# intanRHS2116.net
KiCad netlist of a schematic drawn in Altium Designer
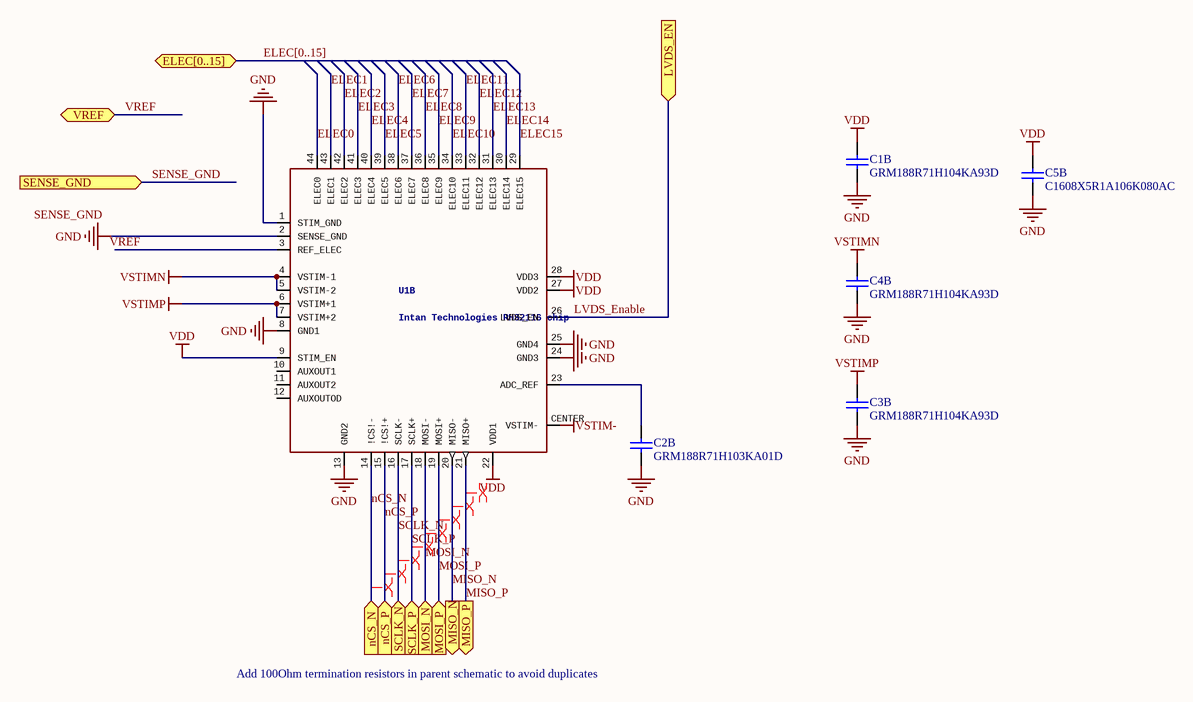
[diagram p0: intanRHS2116.SchDoc]

(export (version "E")
  (design (tool "Eeschema 10.0.6"))
  (components
    (comp (ref "C1B")
      (value "GRM188R71H104KA93D")
      (footprint "CAPC1608X90X35ML10T15")
      (description "Chip Capacitor, 0.1 uF, +/- 10%, 50 V, -55 to 125 degC, 0603 (1608 Metric), RoHS, Tape and Reel")
      (fields (field (name "TOLERANCE") "10%") (field (name "VOLTAGE") "50V"))
      (libsource (lib "Altium Content Vault") (part "CAP-NP-2"))
    )
    (comp (ref "C2B")
      (value "GRM188R71H103KA01D")
      (footprint "CAPC1608X90X35ML10T15")
      (description "Chip Capacitor, 10 nF, +/- 10%, 50 V, -55 to 125 degC, 0603 (1608 Metric), RoHS, Tape and Reel")
      (fields (field (name "VOLTAGE") "50V") (field (name "TOLERANCE") "10%"))
      (libsource (lib "Altium Content Vault") (part "CAP-NP-2"))
    )
    (comp (ref "C3B")
      (value "GRM188R71H104KA93D")
      (footprint "CAPC1608X90X35ML10T15")
      (description "Chip Capacitor, 0.1 uF, +/- 10%, 50 V, -55 to 125 degC, 0603 (1608 Metric), RoHS, Tape and Reel")
      (fields (field (name "TOLERANCE") "10%") (field (name "VOLTAGE") "50V"))
      (libsource (lib "Altium Content Vault") (part "CAP-NP-2"))
    )
    (comp (ref "C4B")
      (value "GRM188R71H104KA93D")
      (footprint "CAPC1608X90X35ML10T15")
      (description "Chip Capacitor, 0.1 uF, +/- 10%, 50 V, -55 to 125 degC, 0603 (1608 Metric), RoHS, Tape and Reel")
      (fields (field (name "TOLERANCE") "10%") (field (name "VOLTAGE") "50V"))
      (libsource (lib "Altium Content Vault") (part "CAP-NP-2"))
    )
    (comp (ref "C5B")
      (value "C1608X5R1A106K080AC")
      (footprint "CAPC1608X90X20ML10")
      (description "Chip Capacitor, 10 uF, +/- 10%, 10 V, -55 to 85 degC, 0603 (1608 Metric), RoHS, Tape and Reel")
      (fields
        (field (name "PCN PART NUMBER") "MLCCPartNumberChange30/Nov/2012")
        (field (name "TOLERANCE") "±10%")
      )
      (libsource (lib "Altium Content Vault") (part "CAP-NP-2"))
    )
    (comp (ref "U1B")
      (value "Intan Technologies RHS2116 chip")
      (footprint "intan_rhs2116:QFN44_7_X_7")
      (fields
        (field (name "MANUFACTURER") "Intan Technologies")
        (field (name "MANUFACTURER PART NUMBER") "RHS2116")
      )
      (libsource (lib "intan_rhs2116") (part "RHS2116_QFN"))
    )
  )
  (nets
    (net (code "1") (name "/ELEC0") (class "Default")
      (node (ref "U1B") (pin "44") (pinfunction "ELEC0_44") (pintype "passive"))
    )
    (net (code "2") (name "/ELEC1") (class "Default")
      (node (ref "U1B") (pin "43") (pinfunction "ELEC1_43") (pintype "passive"))
    )
    (net (code "3") (name "/ELEC2") (class "Default")
      (node (ref "U1B") (pin "42") (pinfunction "ELEC2_42") (pintype "passive"))
    )
    (net (code "4") (name "/ELEC3") (class "Default")
      (node (ref "U1B") (pin "41") (pinfunction "ELEC3_41") (pintype "passive"))
    )
    (net (code "5") (name "/ELEC4") (class "Default")
      (node (ref "U1B") (pin "40") (pinfunction "ELEC4_40") (pintype "passive"))
    )
    (net (code "6") (name "/ELEC5") (class "Default")
      (node (ref "U1B") (pin "39") (pinfunction "ELEC5_39") (pintype "passive"))
    )
    (net (code "7") (name "/ELEC6") (class "Default")
      (node (ref "U1B") (pin "38") (pinfunction "ELEC6_38") (pintype "passive"))
    )
    (net (code "8") (name "/ELEC7") (class "Default")
      (node (ref "U1B") (pin "37") (pinfunction "ELEC7_37") (pintype "passive"))
    )
    (net (code "9") (name "/ELEC8") (class "Default")
      (node (ref "U1B") (pin "36") (pinfunction "ELEC8_36") (pintype "passive"))
    )
    (net (code "10") (name "/ELEC9") (class "Default")
      (node (ref "U1B") (pin "35") (pinfunction "ELEC9_35") (pintype "passive"))
    )
    (net (code "11") (name "/ELEC10") (class "Default")
      (node (ref "U1B") (pin "34") (pinfunction "ELEC10_34") (pintype "passive"))
    )
    (net (code "12") (name "/ELEC11") (class "Default")
      (node (ref "U1B") (pin "33") (pinfunction "ELEC11_33") (pintype "passive"))
    )
    (net (code "13") (name "/ELEC12") (class "Default")
      (node (ref "U1B") (pin "32") (pinfunction "ELEC12_32") (pintype "passive"))
    )
    (net (code "14") (name "/ELEC13") (class "Default")
      (node (ref "U1B") (pin "31") (pinfunction "ELEC13_31") (pintype "passive"))
    )
    (net (code "15") (name "/ELEC14") (class "Default")
      (node (ref "U1B") (pin "30") (pinfunction "ELEC14_30") (pintype "passive"))
    )
    (net (code "16") (name "/ELEC15") (class "Default")
      (node (ref "U1B") (pin "29") (pinfunction "ELEC15_29") (pintype "passive"))
    )
    (net (code "18") (name "/LVDS_Enable") (class "Default")
      (node (ref "U1B") (pin "26") (pinfunction "LVDS_EN_26") (pintype "passive"))
    )
    (net (code "19") (name "/MISO_N") (class "Default")
      (node (ref "U1B") (pin "20") (pinfunction "MISO-_20") (pintype "output"))
    )
    (net (code "20") (name "/MISO_P") (class "Default")
      (node (ref "U1B") (pin "21") (pinfunction "MISO+_21") (pintype "output"))
    )
    (net (code "21") (name "/MOSI_N") (class "Default")
      (node (ref "U1B") (pin "18") (pinfunction "MOSI-_18") (pintype "passive"))
    )
    (net (code "22") (name "/MOSI_P") (class "Default")
      (node (ref "U1B") (pin "19") (pinfunction "MOSI+_19") (pintype "passive"))
    )
    (net (code "23") (name "/SCLK_N") (class "Default")
      (node (ref "U1B") (pin "16") (pinfunction "SCLK-_16") (pintype "passive"))
    )
    (net (code "24") (name "/SCLK_P") (class "Default")
      (node (ref "U1B") (pin "17") (pinfunction "SCLK+_17") (pintype "passive"))
    )
    (net (code "26") (name "/VREF") (class "Default")
      (node (ref "U1B") (pin "3") (pinfunction "REF_ELEC_3") (pintype "passive"))
    )
    (net (code "27") (name "/nCS_N") (class "Default")
      (node (ref "U1B") (pin "14") (pinfunction "!CS!-_14") (pintype "passive"))
    )
    (net (code "28") (name "/nCS_P") (class "Default")
      (node (ref "U1B") (pin "15") (pinfunction "!CS!+_15") (pintype "passive"))
    )
    (net (code "29") (name "GND") (class "Default")
      (node (ref "C1B") (pin "1") (pinfunction "1_1") (pintype "passive"))
      (node (ref "C2B") (pin "1") (pinfunction "1_1") (pintype "passive"))
      (node (ref "C3B") (pin "1") (pinfunction "1_1") (pintype "passive"))
      (node (ref "C4B") (pin "1") (pinfunction "1_1") (pintype "passive"))
      (node (ref "C5B") (pin "1") (pinfunction "1_1") (pintype "passive"))
      (node (ref "U1B") (pin "1") (pinfunction "STIM_GND_1") (pintype "power_in"))
      (node (ref "U1B") (pin "13") (pinfunction "GND2_13") (pintype "power_in"))
      (node (ref "U1B") (pin "2") (pinfunction "SENSE_GND_2") (pintype "power_in"))
      (node (ref "U1B") (pin "24") (pinfunction "GND3_24") (pintype "power_in"))
      (node (ref "U1B") (pin "25") (pinfunction "GND4_25") (pintype "power_in"))
      (node (ref "U1B") (pin "8") (pinfunction "GND1_8") (pintype "power_in"))
    )
    (net (code "30") (name "Net-(U1B-ADC_REF)") (class "Default")
      (node (ref "C2B") (pin "2") (pinfunction "2_2") (pintype "passive"))
      (node (ref "U1B") (pin "23") (pinfunction "ADC_REF_23") (pintype "passive"))
    )
    (net (code "31") (name "VDD") (class "Default")
      (node (ref "C1B") (pin "2") (pinfunction "2_2") (pintype "passive"))
      (node (ref "C5B") (pin "2") (pinfunction "2_2") (pintype "passive"))
      (node (ref "U1B") (pin "22") (pinfunction "VDD1_22") (pintype "power_in"))
      (node (ref "U1B") (pin "27") (pinfunction "VDD2_27") (pintype "power_in"))
      (node (ref "U1B") (pin "28") (pinfunction "VDD3_28") (pintype "power_in"))
      (node (ref "U1B") (pin "9") (pinfunction "STIM_EN_9") (pintype "passive"))
    )
    (net (code "32") (name "VSTIM-") (class "Default")
      (node (ref "U1B") (pin "CENTER") (pinfunction "VSTIM-_CENTER") (pintype "power_in"))
    )
    (net (code "33") (name "VSTIMN") (class "Default")
      (node (ref "C4B") (pin "2") (pinfunction "2_2") (pintype "passive"))
      (node (ref "U1B") (pin "4") (pinfunction "VSTIM-1_4") (pintype "power_in"))
      (node (ref "U1B") (pin "5") (pinfunction "VSTIM-2_5") (pintype "power_in"))
    )
    (net (code "34") (name "VSTIMP") (class "Default")
      (node (ref "C3B") (pin "2") (pinfunction "2_2") (pintype "passive"))
      (node (ref "U1B") (pin "6") (pinfunction "VSTIM+1_6") (pintype "power_in"))
      (node (ref "U1B") (pin "7") (pinfunction "VSTIM+2_7") (pintype "power_in"))
    )
    (net (code "35") (name "unconnected-(U1B-AUXOUT1-Pad10)") (class "Default")
      (node (ref "U1B") (pin "10") (pinfunction "AUXOUT1_10") (pintype "tri_state"))
    )
    (net (code "36") (name "unconnected-(U1B-AUXOUT2-Pad11)") (class "Default")
      (node (ref "U1B") (pin "11") (pinfunction "AUXOUT2_11") (pintype "tri_state"))
    )
    (net (code "37") (name "unconnected-(U1B-AUXOUTOD-Pad12)") (class "Default")
      (node (ref "U1B") (pin "12") (pinfunction "AUXOUTOD_12") (pintype "open_collector"))
    )
  )
)
